# siggen.net
KiCad netlist of a schematic drawn in EAGLE
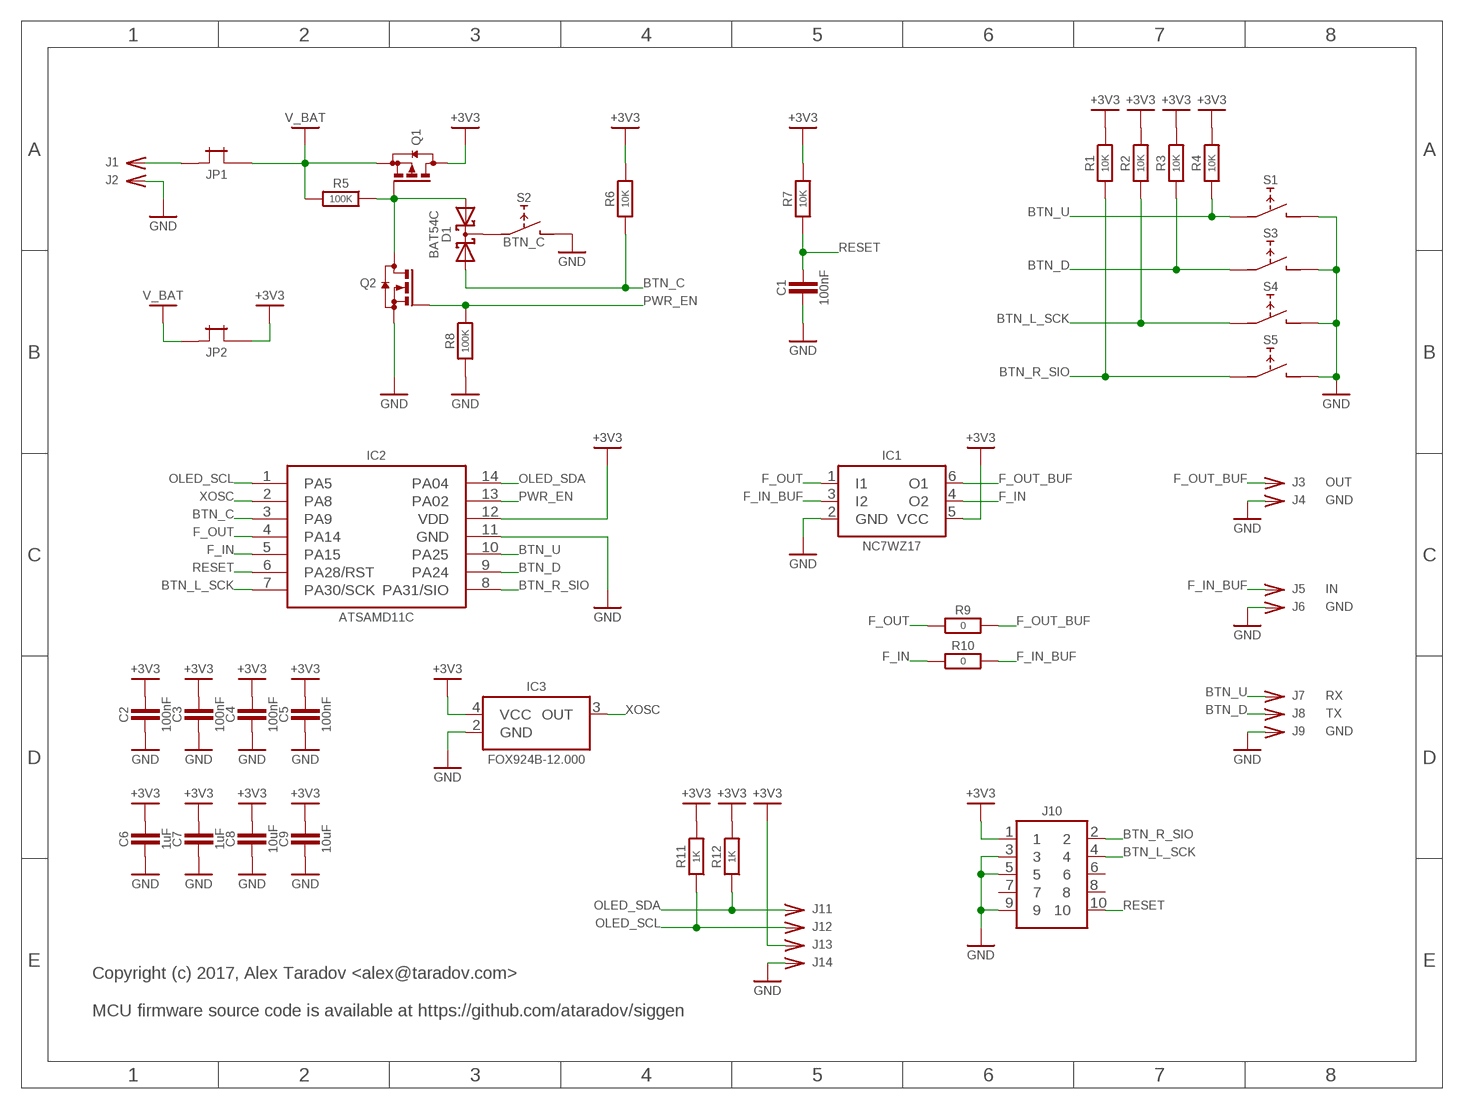
[diagram p0: schematic, sheet 1]

(export (version "E")
  (design (tool "Eeschema 10.0.6"))
  (components
    (comp (ref "C1")
      (value "100nF")
      (footprint "eagle-import:SMD0603")
      (libsource (lib "eagle-import") (part "C-0603"))
    )
    (comp (ref "C2")
      (value "100nF")
      (footprint "eagle-import:SMD0603")
      (libsource (lib "eagle-import") (part "C-0603"))
    )
    (comp (ref "C3")
      (value "100nF")
      (footprint "eagle-import:SMD0603")
      (libsource (lib "eagle-import") (part "C-0603"))
    )
    (comp (ref "C4")
      (value "100nF")
      (footprint "eagle-import:SMD0603")
      (libsource (lib "eagle-import") (part "C-0603"))
    )
    (comp (ref "C5")
      (value "100nF")
      (footprint "eagle-import:SMD0603")
      (libsource (lib "eagle-import") (part "C-0603"))
    )
    (comp (ref "C6")
      (value "1uF")
      (footprint "eagle-import:SMD0603")
      (libsource (lib "eagle-import") (part "C-0603"))
    )
    (comp (ref "C7")
      (value "1uF")
      (footprint "eagle-import:SMD0603")
      (libsource (lib "eagle-import") (part "C-0603"))
    )
    (comp (ref "C8")
      (value "10uF")
      (footprint "eagle-import:SMD0805")
      (libsource (lib "eagle-import") (part "C-0805"))
    )
    (comp (ref "C9")
      (value "10uF")
      (footprint "eagle-import:SMD0805")
      (libsource (lib "eagle-import") (part "C-0805"))
    )
    (comp (ref "D1")
      (value "BAT54C")
      (footprint "eagle-import:SOT23")
      (libsource (lib "eagle-import") (part "BAT54C"))
    )
    (comp (ref "IC1")
      (value "NC7WZ17")
      (footprint "eagle-import:SC70")
      (libsource (lib "eagle-import") (part "NC7WZ17"))
    )
    (comp (ref "IC2")
      (value "ATSAMD11C")
      (footprint "eagle-import:SO-14")
      (libsource (lib "eagle-import") (part "ATSAMD11C"))
    )
    (comp (ref "IC3")
      (value "FOX924B-12.000")
      (footprint "eagle-import:CTS406")
      (libsource (lib "eagle-import") (part "OSC-CTS406"))
    )
    (comp (ref "J1")
      (value "CONN-SINGLE-TH")
      (footprint "eagle-import:PIN-TH")
      (libsource (lib "eagle-import") (part "CONN-SINGLE-TH"))
    )
    (comp (ref "J2")
      (value "CONN-SINGLE-TH")
      (footprint "eagle-import:PIN-TH")
      (libsource (lib "eagle-import") (part "CONN-SINGLE-TH"))
    )
    (comp (ref "J3")
      (value "OUT")
      (footprint "eagle-import:PIN-TH")
      (libsource (lib "eagle-import") (part "CONN-SINGLE-TH"))
    )
    (comp (ref "J4")
      (value "GND")
      (footprint "eagle-import:PIN-TH")
      (libsource (lib "eagle-import") (part "CONN-SINGLE-TH"))
    )
    (comp (ref "J5")
      (value "IN")
      (footprint "eagle-import:PIN-TH")
      (libsource (lib "eagle-import") (part "CONN-SINGLE-TH"))
    )
    (comp (ref "J6")
      (value "GND")
      (footprint "eagle-import:PIN-TH")
      (libsource (lib "eagle-import") (part "CONN-SINGLE-TH"))
    )
    (comp (ref "J7")
      (value "RX")
      (footprint "eagle-import:PIN-TH")
      (libsource (lib "eagle-import") (part "CONN-SINGLE-TH"))
    )
    (comp (ref "J8")
      (value "TX")
      (footprint "eagle-import:PIN-TH")
      (libsource (lib "eagle-import") (part "CONN-SINGLE-TH"))
    )
    (comp (ref "J9")
      (value "GND")
      (footprint "eagle-import:PIN-TH")
      (libsource (lib "eagle-import") (part "CONN-SINGLE-TH"))
    )
    (comp (ref "J10")
      (value "HEADER-5X2-TH-1.27")
      (footprint "eagle-import:HEADER-5X2-1.27MM")
      (libsource (lib "eagle-import") (part "HEADER-5X2-TH-1.27"))
    )
    (comp (ref "J11")
      (value "CONN-SINGLE-TH")
      (footprint "eagle-import:PIN-TH")
      (libsource (lib "eagle-import") (part "CONN-SINGLE-TH"))
    )
    (comp (ref "J12")
      (value "CONN-SINGLE-TH")
      (footprint "eagle-import:PIN-TH")
      (libsource (lib "eagle-import") (part "CONN-SINGLE-TH"))
    )
    (comp (ref "J13")
      (value "CONN-SINGLE-TH")
      (footprint "eagle-import:PIN-TH")
      (libsource (lib "eagle-import") (part "CONN-SINGLE-TH"))
    )
    (comp (ref "J14")
      (value "CONN-SINGLE-TH")
      (footprint "eagle-import:PIN-TH")
      (libsource (lib "eagle-import") (part "CONN-SINGLE-TH"))
    )
    (comp (ref "JP1")
      (value "JUMPER-TH-TH")
      (footprint "eagle-import:JUMPER-TH")
      (libsource (lib "eagle-import") (part "JUMPER-TH-TH"))
    )
    (comp (ref "JP2")
      (value "JUMPER-TH-TH")
      (footprint "eagle-import:JUMPER-TH")
      (libsource (lib "eagle-import") (part "JUMPER-TH-TH"))
    )
    (comp (ref "Q1")
      (value "P-MOSFET")
      (footprint "eagle-import:SOT23")
      (libsource (lib "eagle-import") (part "P-MOSFET"))
    )
    (comp (ref "Q2")
      (value "N-MOSFET")
      (footprint "eagle-import:SOT23")
      (libsource (lib "eagle-import") (part "N-MOSFET"))
    )
    (comp (ref "R1")
      (value "10K")
      (footprint "eagle-import:SMD0603")
      (libsource (lib "eagle-import") (part "R-0603"))
    )
    (comp (ref "R2")
      (value "10K")
      (footprint "eagle-import:SMD0603")
      (libsource (lib "eagle-import") (part "R-0603"))
    )
    (comp (ref "R3")
      (value "10K")
      (footprint "eagle-import:SMD0603")
      (libsource (lib "eagle-import") (part "R-0603"))
    )
    (comp (ref "R4")
      (value "10K")
      (footprint "eagle-import:SMD0603")
      (libsource (lib "eagle-import") (part "R-0603"))
    )
    (comp (ref "R5")
      (value "100K")
      (footprint "eagle-import:SMD0603")
      (libsource (lib "eagle-import") (part "R-0603"))
    )
    (comp (ref "R6")
      (value "10K")
      (footprint "eagle-import:SMD0603")
      (libsource (lib "eagle-import") (part "R-0603"))
    )
    (comp (ref "R7")
      (value "10K")
      (footprint "eagle-import:SMD0603")
      (libsource (lib "eagle-import") (part "R-0603"))
    )
    (comp (ref "R8")
      (value "100K")
      (footprint "eagle-import:SMD0603")
      (libsource (lib "eagle-import") (part "R-0603"))
    )
    (comp (ref "R9")
      (value "0")
      (footprint "eagle-import:SMD0603")
      (libsource (lib "eagle-import") (part "R-0603"))
    )
    (comp (ref "R10")
      (value "0")
      (footprint "eagle-import:SMD0603")
      (libsource (lib "eagle-import") (part "R-0603"))
    )
    (comp (ref "R11")
      (value "1K")
      (footprint "eagle-import:SMD0603")
      (libsource (lib "eagle-import") (part "R-0603"))
    )
    (comp (ref "R12")
      (value "1K")
      (footprint "eagle-import:SMD0603")
      (libsource (lib "eagle-import") (part "R-0603"))
    )
    (comp (ref "S1")
      (value "TACT_SWITCH_6MM-SMD")
      (footprint "eagle-import:TACT-SMD-6MM")
      (libsource (lib "eagle-import") (part "TACT_SWITCH_6MM-SMD"))
    )
    (comp (ref "S2")
      (value "BTN_C")
      (footprint "eagle-import:TACT-SMD-6MM")
      (libsource (lib "eagle-import") (part "TACT_SWITCH_6MM-SMD"))
    )
    (comp (ref "S3")
      (value "TACT_SWITCH_6MM-SMD")
      (footprint "eagle-import:TACT-SMD-6MM")
      (libsource (lib "eagle-import") (part "TACT_SWITCH_6MM-SMD"))
    )
    (comp (ref "S4")
      (value "TACT_SWITCH_6MM-SMD")
      (footprint "eagle-import:TACT-SMD-6MM")
      (libsource (lib "eagle-import") (part "TACT_SWITCH_6MM-SMD"))
    )
    (comp (ref "S5")
      (value "TACT_SWITCH_6MM-SMD")
      (footprint "eagle-import:TACT-SMD-6MM")
      (libsource (lib "eagle-import") (part "TACT_SWITCH_6MM-SMD"))
    )
  )
  (nets
    (net (code "1") (name "+3V3") (class "Default")
      (node (ref "C2") (pin "2") (pinfunction "2_2") (pintype "passive"))
      (node (ref "C3") (pin "2") (pinfunction "2_2") (pintype "passive"))
      (node (ref "C4") (pin "2") (pinfunction "2_2") (pintype "passive"))
      (node (ref "C5") (pin "2") (pinfunction "2_2") (pintype "passive"))
      (node (ref "C6") (pin "2") (pinfunction "2_2") (pintype "passive"))
      (node (ref "C7") (pin "2") (pinfunction "2_2") (pintype "passive"))
      (node (ref "C8") (pin "2") (pinfunction "2_2") (pintype "passive"))
      (node (ref "C9") (pin "2") (pinfunction "2_2") (pintype "passive"))
      (node (ref "IC1") (pin "5") (pinfunction "VCC_5") (pintype "power_in"))
      (node (ref "IC2") (pin "12") (pinfunction "VDD_12") (pintype "bidirectional"))
      (node (ref "IC3") (pin "4") (pinfunction "VCC_4") (pintype "power_in"))
      (node (ref "J10") (pin "1") (pinfunction "1_1") (pintype "passive"))
      (node (ref "J13") (pin "1") (pinfunction "1_1") (pintype "passive"))
      (node (ref "JP2") (pin "2") (pinfunction "2_2") (pintype "passive"))
      (node (ref "Q1") (pin "3") (pinfunction "D_3") (pintype "passive"))
      (node (ref "R1") (pin "2") (pinfunction "2_2") (pintype "passive"))
      (node (ref "R11") (pin "2") (pinfunction "2_2") (pintype "passive"))
      (node (ref "R12") (pin "2") (pinfunction "2_2") (pintype "passive"))
      (node (ref "R2") (pin "2") (pinfunction "2_2") (pintype "passive"))
      (node (ref "R3") (pin "2") (pinfunction "2_2") (pintype "passive"))
      (node (ref "R4") (pin "2") (pinfunction "2_2") (pintype "passive"))
      (node (ref "R6") (pin "2") (pinfunction "2_2") (pintype "passive"))
      (node (ref "R7") (pin "2") (pinfunction "2_2") (pintype "passive"))
    )
    (net (code "2") (name "/BTN_C") (class "Default")
      (node (ref "D1") (pin "1") (pinfunction "A1_1") (pintype "passive"))
      (node (ref "IC2") (pin "3") (pinfunction "PA9_3") (pintype "bidirectional"))
      (node (ref "R6") (pin "1") (pinfunction "1_1") (pintype "passive"))
    )
    (net (code "3") (name "/BTN_D") (class "Default")
      (node (ref "IC2") (pin "9") (pinfunction "PA24_9") (pintype "bidirectional"))
      (node (ref "J8") (pin "1") (pinfunction "1_1") (pintype "passive"))
      (node (ref "R3") (pin "1") (pinfunction "1_1") (pintype "passive"))
      (node (ref "S3") (pin "1") (pinfunction "1_1") (pintype "passive"))
      (node (ref "S3") (pin "2") (pinfunction "1_2") (pintype "passive"))
    )
    (net (code "4") (name "/BTN_L_SCK") (class "Default")
      (node (ref "IC2") (pin "7") (pinfunction "PA30/SCK_7") (pintype "bidirectional"))
      (node (ref "J10") (pin "4") (pinfunction "4_4") (pintype "passive"))
      (node (ref "R2") (pin "1") (pinfunction "1_1") (pintype "passive"))
      (node (ref "S4") (pin "1") (pinfunction "1_1") (pintype "passive"))
      (node (ref "S4") (pin "2") (pinfunction "1_2") (pintype "passive"))
    )
    (net (code "5") (name "/BTN_R_SIO") (class "Default")
      (node (ref "IC2") (pin "8") (pinfunction "PA31/SIO_8") (pintype "bidirectional"))
      (node (ref "J10") (pin "2") (pinfunction "2_2") (pintype "passive"))
      (node (ref "R1") (pin "1") (pinfunction "1_1") (pintype "passive"))
      (node (ref "S5") (pin "1") (pinfunction "1_1") (pintype "passive"))
      (node (ref "S5") (pin "2") (pinfunction "1_2") (pintype "passive"))
    )
    (net (code "6") (name "/BTN_U") (class "Default")
      (node (ref "IC2") (pin "10") (pinfunction "PA25_10") (pintype "bidirectional"))
      (node (ref "J7") (pin "1") (pinfunction "1_1") (pintype "passive"))
      (node (ref "R4") (pin "1") (pinfunction "1_1") (pintype "passive"))
      (node (ref "S1") (pin "1") (pinfunction "1_1") (pintype "passive"))
      (node (ref "S1") (pin "2") (pinfunction "1_2") (pintype "passive"))
    )
    (net (code "7") (name "/F_IN") (class "Default")
      (node (ref "IC1") (pin "4") (pinfunction "O2_4") (pintype "output"))
      (node (ref "IC2") (pin "5") (pinfunction "PA15_5") (pintype "bidirectional"))
      (node (ref "R10") (pin "1") (pinfunction "1_1") (pintype "passive"))
    )
    (net (code "8") (name "/F_IN_BUF") (class "Default")
      (node (ref "IC1") (pin "3") (pinfunction "I2_3") (pintype "input"))
      (node (ref "J5") (pin "1") (pinfunction "1_1") (pintype "passive"))
      (node (ref "R10") (pin "2") (pinfunction "2_2") (pintype "passive"))
    )
    (net (code "9") (name "/F_OUT") (class "Default")
      (node (ref "IC1") (pin "1") (pinfunction "I1_1") (pintype "input"))
      (node (ref "IC2") (pin "4") (pinfunction "PA14_4") (pintype "bidirectional"))
      (node (ref "R9") (pin "1") (pinfunction "1_1") (pintype "passive"))
    )
    (net (code "10") (name "/F_OUT_BUF") (class "Default")
      (node (ref "IC1") (pin "6") (pinfunction "O1_6") (pintype "output"))
      (node (ref "J3") (pin "1") (pinfunction "1_1") (pintype "passive"))
      (node (ref "R9") (pin "2") (pinfunction "2_2") (pintype "passive"))
    )
    (net (code "11") (name "/OLED_SCL") (class "Default")
      (node (ref "IC2") (pin "1") (pinfunction "PA5_1") (pintype "bidirectional"))
      (node (ref "J12") (pin "1") (pinfunction "1_1") (pintype "passive"))
      (node (ref "R11") (pin "1") (pinfunction "1_1") (pintype "passive"))
    )
    (net (code "12") (name "/OLED_SDA") (class "Default")
      (node (ref "IC2") (pin "14") (pinfunction "PA04_14") (pintype "bidirectional"))
      (node (ref "J11") (pin "1") (pinfunction "1_1") (pintype "passive"))
      (node (ref "R12") (pin "1") (pinfunction "1_1") (pintype "passive"))
    )
    (net (code "13") (name "/PWR_EN") (class "Default")
      (node (ref "IC2") (pin "13") (pinfunction "PA02_13") (pintype "bidirectional"))
      (node (ref "Q2") (pin "1") (pinfunction "G_1") (pintype "passive"))
      (node (ref "R8") (pin "2") (pinfunction "2_2") (pintype "passive"))
    )
    (net (code "14") (name "/RESET") (class "Default")
      (node (ref "C1") (pin "2") (pinfunction "2_2") (pintype "passive"))
      (node (ref "IC2") (pin "6") (pinfunction "PA28/RST_6") (pintype "bidirectional"))
      (node (ref "J10") (pin "10") (pinfunction "10_10") (pintype "passive"))
      (node (ref "R7") (pin "1") (pinfunction "1_1") (pintype "passive"))
    )
    (net (code "15") (name "/XOSC") (class "Default")
      (node (ref "IC2") (pin "2") (pinfunction "PA8_2") (pintype "bidirectional"))
      (node (ref "IC3") (pin "3") (pinfunction "OUT_3") (pintype "output"))
    )
    (net (code "16") (name "GND") (class "Default")
      (node (ref "C1") (pin "1") (pinfunction "1_1") (pintype "passive"))
      (node (ref "C2") (pin "1") (pinfunction "1_1") (pintype "passive"))
      (node (ref "C3") (pin "1") (pinfunction "1_1") (pintype "passive"))
      (node (ref "C4") (pin "1") (pinfunction "1_1") (pintype "passive"))
      (node (ref "C5") (pin "1") (pinfunction "1_1") (pintype "passive"))
      (node (ref "C6") (pin "1") (pinfunction "1_1") (pintype "passive"))
      (node (ref "C7") (pin "1") (pinfunction "1_1") (pintype "passive"))
      (node (ref "C8") (pin "1") (pinfunction "1_1") (pintype "passive"))
      (node (ref "C9") (pin "1") (pinfunction "1_1") (pintype "passive"))
      (node (ref "IC1") (pin "2") (pinfunction "GND_2") (pintype "power_in"))
      (node (ref "IC2") (pin "11") (pinfunction "GND_11") (pintype "bidirectional"))
      (node (ref "IC3") (pin "2") (pinfunction "GND_2") (pintype "power_in"))
      (node (ref "J10") (pin "3") (pinfunction "3_3") (pintype "passive"))
      (node (ref "J10") (pin "5") (pinfunction "5_5") (pintype "passive"))
      (node (ref "J10") (pin "9") (pinfunction "9_9") (pintype "passive"))
      (node (ref "J14") (pin "1") (pinfunction "1_1") (pintype "passive"))
      (node (ref "J2") (pin "1") (pinfunction "1_1") (pintype "passive"))
      (node (ref "J4") (pin "1") (pinfunction "1_1") (pintype "passive"))
      (node (ref "J6") (pin "1") (pinfunction "1_1") (pintype "passive"))
      (node (ref "J9") (pin "1") (pinfunction "1_1") (pintype "passive"))
      (node (ref "Q2") (pin "2") (pinfunction "S_2") (pintype "passive"))
      (node (ref "R8") (pin "1") (pinfunction "1_1") (pintype "passive"))
      (node (ref "S1") (pin "3") (pinfunction "2_3") (pintype "passive"))
      (node (ref "S1") (pin "4") (pinfunction "2_4") (pintype "passive"))
      (node (ref "S2") (pin "3") (pinfunction "2_3") (pintype "passive"))
      (node (ref "S2") (pin "4") (pinfunction "2_4") (pintype "passive"))
      (node (ref "S3") (pin "3") (pinfunction "2_3") (pintype "passive"))
      (node (ref "S3") (pin "4") (pinfunction "2_4") (pintype "passive"))
      (node (ref "S4") (pin "3") (pinfunction "2_3") (pintype "passive"))
      (node (ref "S4") (pin "4") (pinfunction "2_4") (pintype "passive"))
      (node (ref "S5") (pin "3") (pinfunction "2_3") (pintype "passive"))
      (node (ref "S5") (pin "4") (pinfunction "2_4") (pintype "passive"))
    )
    (net (code "17") (name "Net-(D1-A2)") (class "Default")
      (node (ref "D1") (pin "2") (pinfunction "A2_2") (pintype "passive"))
      (node (ref "Q1") (pin "1") (pinfunction "G_1") (pintype "passive"))
      (node (ref "Q2") (pin "3") (pinfunction "D_3") (pintype "passive"))
      (node (ref "R5") (pin "2") (pinfunction "2_2") (pintype "passive"))
    )
    (net (code "18") (name "Net-(D1-CC)") (class "Default")
      (node (ref "D1") (pin "3") (pinfunction "CC_3") (pintype "passive"))
      (node (ref "S2") (pin "1") (pinfunction "1_1") (pintype "passive"))
      (node (ref "S2") (pin "2") (pinfunction "1_2") (pintype "passive"))
    )
    (net (code "19") (name "Net-(J1-Pad1)") (class "Default")
      (node (ref "J1") (pin "1") (pinfunction "1_1") (pintype "passive"))
      (node (ref "JP1") (pin "1") (pinfunction "1_1") (pintype "passive"))
    )
    (net (code "20") (name "V_BAT") (class "Default")
      (node (ref "JP1") (pin "2") (pinfunction "2_2") (pintype "passive"))
      (node (ref "JP2") (pin "1") (pinfunction "1_1") (pintype "passive"))
      (node (ref "Q1") (pin "2") (pinfunction "S_2") (pintype "passive"))
      (node (ref "R5") (pin "1") (pinfunction "1_1") (pintype "passive"))
    )
    (net (code "21") (name "unconnected-(J10-Pad6)") (class "Default")
      (node (ref "J10") (pin "6") (pinfunction "6_6") (pintype "passive"))
    )
    (net (code "22") (name "unconnected-(J10-Pad7)") (class "Default")
      (node (ref "J10") (pin "7") (pinfunction "7_7") (pintype "passive"))
    )
    (net (code "23") (name "unconnected-(J10-Pad8)") (class "Default")
      (node (ref "J10") (pin "8") (pinfunction "8_8") (pintype "passive"))
    )
  )
)
